# Digital_Input.net
KiCad netlist of a schematic drawn in Altium Designer
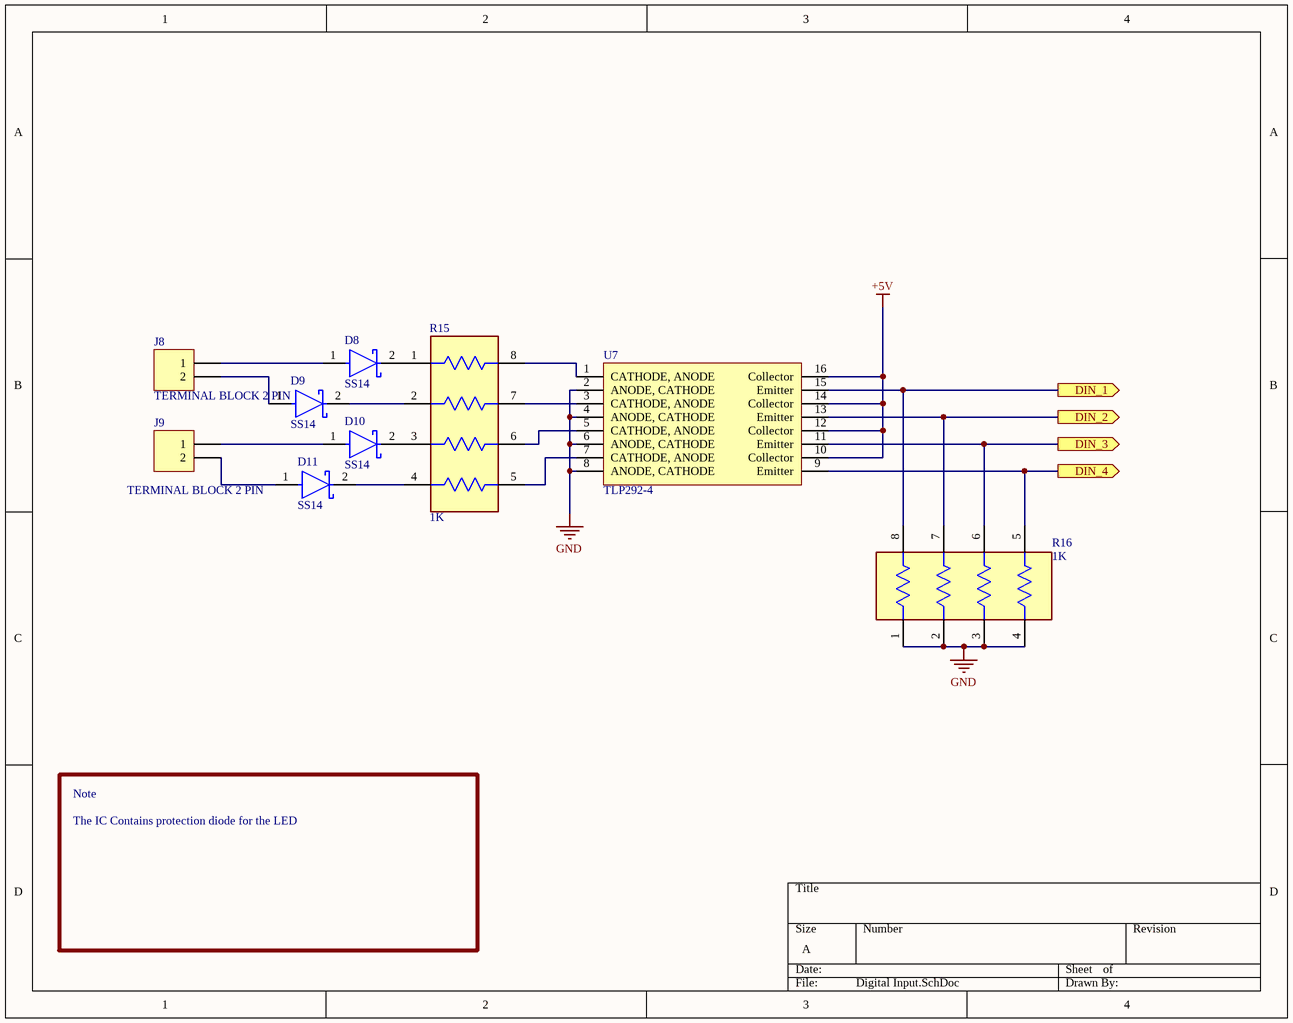
[diagram p0: Digital Input.SchDoc]

(export (version "E")
  (design (tool "Eeschema 10.0.6"))
  (components
    (comp (ref "D8")
      (value "SS14")
      (footprint "FP-403AE-MFG")
      (description "DIODE SCHOTTKY 40V 1A SMA")
      (fields
        (field (name "MANUFACTURER") "ON Semiconductor")
        (field (name "OCTOPART") "https://octopart.com/ss14-on+semiconductor-29205033")
      )
      (libsource (lib "TAREKPCBLIB") (part "SS14"))
    )
    (comp (ref "D9")
      (value "SS14")
      (footprint "FP-403AE-MFG")
      (description "DIODE SCHOTTKY 40V 1A SMA")
      (fields
        (field (name "MANUFACTURER") "ON Semiconductor")
        (field (name "OCTOPART") "https://octopart.com/ss14-on+semiconductor-29205033")
      )
      (libsource (lib "TAREKPCBLIB") (part "SS14"))
    )
    (comp (ref "D10")
      (value "SS14")
      (footprint "FP-403AE-MFG")
      (description "DIODE SCHOTTKY 40V 1A SMA")
      (fields
        (field (name "MANUFACTURER") "ON Semiconductor")
        (field (name "OCTOPART") "https://octopart.com/ss14-on+semiconductor-29205033")
      )
      (libsource (lib "TAREKPCBLIB") (part "SS14"))
    )
    (comp (ref "D11")
      (value "SS14")
      (footprint "FP-403AE-MFG")
      (description "DIODE SCHOTTKY 40V 1A SMA")
      (fields
        (field (name "MANUFACTURER") "ON Semiconductor")
        (field (name "OCTOPART") "https://octopart.com/ss14-on+semiconductor-29205033")
      )
      (libsource (lib "TAREKPCBLIB") (part "SS14"))
    )
    (comp (ref "J8")
      (value "TERMINAL BLOCK 2 PIN")
      (footprint "CON2_P196_1729128_TH_ST")
      (description "2 Pins, 1 Row 5mm Pitch, straight Connector, male")
      (fields
        (field (name "MANUFACTURER") "Phoenix Contact")
        (field (name "MANUFACTURER PART NUMBER") "MKDSN1,5/2")
      )
      (libsource (lib "ESTEEMPCBLIB") (part "CON-TB_2X1-196-ST-TH"))
    )
    (comp (ref "J9")
      (value "TERMINAL BLOCK 2 PIN")
      (footprint "CON2_P196_1729128_TH_ST")
      (description "2 Pins, 1 Row 5mm Pitch, straight Connector, male")
      (fields
        (field (name "MANUFACTURER") "Phoenix Contact")
        (field (name "MANUFACTURER PART NUMBER") "MKDSN1,5/2")
      )
      (libsource (lib "ESTEEMPCBLIB") (part "CON-TB_2X1-196-ST-TH"))
    )
    (comp (ref "R15")
      (value "1K")
      (footprint "FP-YC164-MFG")
      (description "RES ARRAY 4 RES 1K OHM 1206")
      (fields (field (name "TOLERANCE") "5%"))
      (libsource (lib "") (part "Res-Array_1"))
    )
    (comp (ref "R16")
      (value "1K")
      (footprint "FP-YC164-MFG")
      (description "RES ARRAY 4 RES 1K OHM 1206")
      (fields (field (name "TOLERANCE") "5%"))
      (libsource (lib "TAREKPCBLIB") (part "Res-Array"))
    )
    (comp (ref "U7")
      (value "TLP292-4")
      (footprint "SOIC16_50_284_25X90_SMT")
      (description "Optoisolator Transistor Output 3750Vrms 4 Channel 16-SO")
      (fields (field (name "MANUFACTURER") "Olimex") (field (name "MANUFACTURER PART NUMBER") "CH340C"))
      (libsource (lib "TAREKPCBLIB") (part "TLP292-4"))
    )
  )
  (nets
    (net (code "1") (name "+5V") (class "Default")
      (node (ref "U7") (pin "10") (pinfunction "Collector_10") (pintype "passive"))
      (node (ref "U7") (pin "12") (pinfunction "Collector_12") (pintype "passive"))
      (node (ref "U7") (pin "14") (pinfunction "Collector_14") (pintype "passive"))
      (node (ref "U7") (pin "16") (pinfunction "Collector_16") (pintype "passive"))
    )
    (net (code "2") (name "/DIN_1") (class "Default")
      (node (ref "R16") (pin "8") (pinfunction "8_8") (pintype "passive"))
      (node (ref "U7") (pin "15") (pinfunction "Emitter_15") (pintype "passive"))
    )
    (net (code "3") (name "/DIN_2") (class "Default")
      (node (ref "R16") (pin "7") (pinfunction "7_7") (pintype "passive"))
      (node (ref "U7") (pin "13") (pinfunction "Emitter_13") (pintype "passive"))
    )
    (net (code "4") (name "/DIN_3") (class "Default")
      (node (ref "R16") (pin "6") (pinfunction "6_6") (pintype "passive"))
      (node (ref "U7") (pin "11") (pinfunction "Emitter_11") (pintype "passive"))
    )
    (net (code "5") (name "/DIN_4") (class "Default")
      (node (ref "R16") (pin "5") (pinfunction "5_5") (pintype "passive"))
      (node (ref "U7") (pin "9") (pinfunction "Emitter_9") (pintype "passive"))
    )
    (net (code "6") (name "GND") (class "Default")
      (node (ref "R16") (pin "1") (pinfunction "1_1") (pintype "passive"))
      (node (ref "R16") (pin "2") (pinfunction "2_2") (pintype "passive"))
      (node (ref "R16") (pin "3") (pinfunction "3_3") (pintype "passive"))
      (node (ref "R16") (pin "4") (pinfunction "4_4") (pintype "passive"))
      (node (ref "U7") (pin "2") (pinfunction "ANODE,_CATHODE_2") (pintype "passive"))
      (node (ref "U7") (pin "4") (pinfunction "ANODE,_CATHODE_4") (pintype "passive"))
      (node (ref "U7") (pin "6") (pinfunction "ANODE,_CATHODE_6") (pintype "passive"))
      (node (ref "U7") (pin "8") (pinfunction "ANODE,_CATHODE_8") (pintype "passive"))
    )
    (net (code "7") (name "Net-(D8-A)") (class "Default")
      (node (ref "D8") (pin "1") (pinfunction "A_1") (pintype "passive"))
      (node (ref "J8") (pin "1") (pinfunction "1_1") (pintype "passive"))
    )
    (net (code "8") (name "Net-(D8-C)") (class "Default")
      (node (ref "D8") (pin "2") (pinfunction "C_2") (pintype "passive"))
      (node (ref "R15") (pin "1") (pinfunction "1_1") (pintype "passive"))
    )
    (net (code "9") (name "Net-(D9-A)") (class "Default")
      (node (ref "D9") (pin "1") (pinfunction "A_1") (pintype "passive"))
      (node (ref "J8") (pin "2") (pinfunction "2_2") (pintype "passive"))
    )
    (net (code "10") (name "Net-(D9-C)") (class "Default")
      (node (ref "D9") (pin "2") (pinfunction "C_2") (pintype "passive"))
      (node (ref "R15") (pin "2") (pinfunction "2_2") (pintype "passive"))
    )
    (net (code "11") (name "Net-(D10-A)") (class "Default")
      (node (ref "D10") (pin "1") (pinfunction "A_1") (pintype "passive"))
      (node (ref "J9") (pin "1") (pinfunction "1_1") (pintype "passive"))
    )
    (net (code "12") (name "Net-(D10-C)") (class "Default")
      (node (ref "D10") (pin "2") (pinfunction "C_2") (pintype "passive"))
      (node (ref "R15") (pin "3") (pinfunction "3_3") (pintype "passive"))
    )
    (net (code "13") (name "Net-(D11-A)") (class "Default")
      (node (ref "D11") (pin "1") (pinfunction "A_1") (pintype "passive"))
      (node (ref "J9") (pin "2") (pinfunction "2_2") (pintype "passive"))
    )
    (net (code "14") (name "Net-(D11-C)") (class "Default")
      (node (ref "D11") (pin "2") (pinfunction "C_2") (pintype "passive"))
      (node (ref "R15") (pin "4") (pinfunction "4_4") (pintype "passive"))
    )
    (net (code "15") (name "Net-(R15-Pad5)") (class "Default")
      (node (ref "R15") (pin "5") (pinfunction "5_5") (pintype "passive"))
      (node (ref "U7") (pin "7") (pinfunction "CATHODE,_ANODE_7") (pintype "passive"))
    )
    (net (code "16") (name "Net-(R15-Pad6)") (class "Default")
      (node (ref "R15") (pin "6") (pinfunction "6_6") (pintype "passive"))
      (node (ref "U7") (pin "5") (pinfunction "CATHODE,_ANODE_5") (pintype "passive"))
    )
    (net (code "17") (name "Net-(R15-Pad7)") (class "Default")
      (node (ref "R15") (pin "7") (pinfunction "7_7") (pintype "passive"))
      (node (ref "U7") (pin "3") (pinfunction "CATHODE,_ANODE_3") (pintype "passive"))
    )
    (net (code "18") (name "Net-(R15-Pad8)") (class "Default")
      (node (ref "R15") (pin "8") (pinfunction "8_8") (pintype "passive"))
      (node (ref "U7") (pin "1") (pinfunction "CATHODE,_ANODE_1") (pintype "passive"))
    )
  )
)
